# Mainboard.net
KiCad netlist of a schematic drawn in Altium Designer
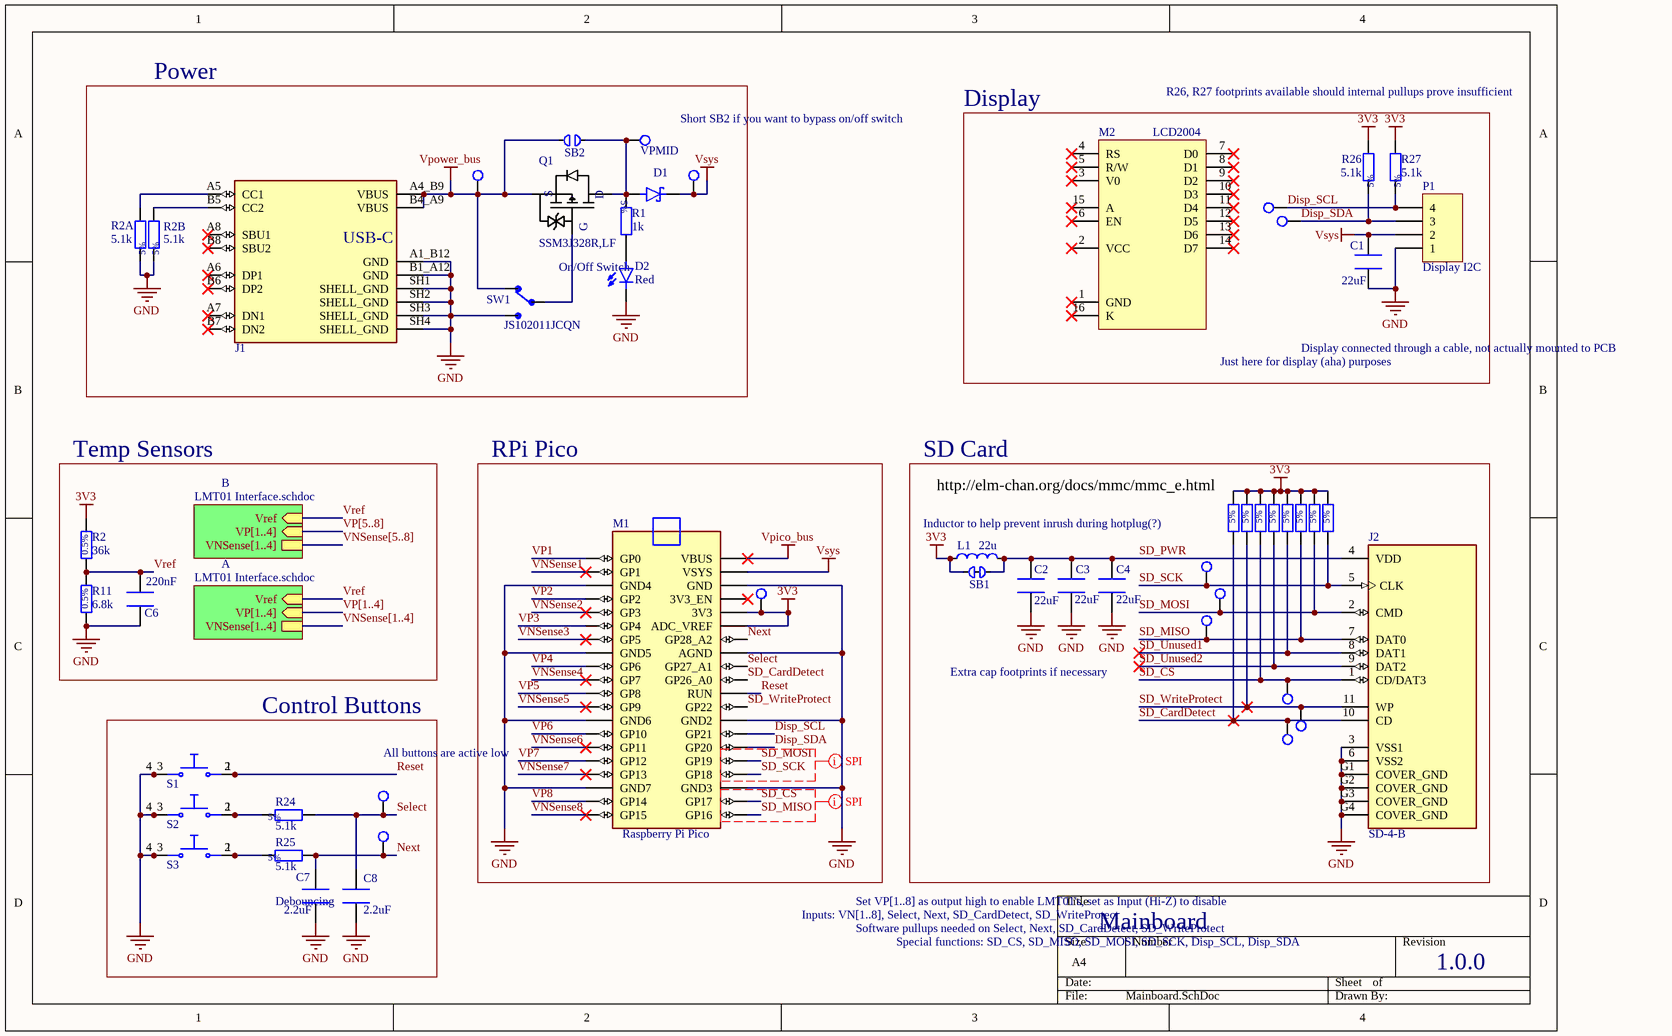
[diagram p0: Mainboard.SchDoc]

(export (version "E")
  (design (tool "Eeschema 10.0.6"))
  (components
    (comp (ref "3V3")
      (value "Test Pad")
      (footprint "Test Pad")
      (libsource (lib "General Components") (part "Test Pad"))
    )
    (comp (ref "C1")
      (value "22uF")
      (footprint "APSS Prototype Parts:CAPACITOR_0805_2012M-70N")
      (description "Passive - Capacitor, X5R, 22uF Max, 6.3V, 0805 (2012 Metric), ±20%, -55°C ~ 85°C. 8.8uF @ 5V")
      (fields (field (name "TOLERANCE") "±20%") (field (name "MF PART NO.") "C0805C226M9PACTU"))
      (libsource (lib "APSS Prototype Parts") (part "C0805C226M9PACTU"))
    )
    (comp (ref "C2")
      (value "22uF")
      (footprint "APSS Prototype Parts:CAPACITOR_0805_2012M-70N")
      (fields
        (field (name "TOLERANCE") "±20%")
        (field (name "MF PART NO.") "GRM21BR61C226ME44L")
        (field (name "APSS STANDARD PART") "APSS Standard")
      )
      (libsource (lib "APSS Prototype Parts") (part "GRM21BR61C226ME44L"))
    )
    (comp (ref "C3")
      (value "22uF")
      (footprint "APSS Prototype Parts:CAPACITOR_0805_2012M-70N")
      (fields
        (field (name "TOLERANCE") "±20%")
        (field (name "MF PART NO.") "GRM21BR61C226ME44L")
        (field (name "APSS STANDARD PART") "APSS Standard")
      )
      (libsource (lib "APSS Prototype Parts") (part "GRM21BR61C226ME44L"))
    )
    (comp (ref "C4")
      (value "22uF")
      (footprint "APSS Prototype Parts:CAPACITOR_0805_2012M-70N")
      (fields
        (field (name "TOLERANCE") "±20%")
        (field (name "MF PART NO.") "GRM21BR61C226ME44L")
        (field (name "APSS STANDARD PART") "APSS Standard")
      )
      (libsource (lib "APSS Prototype Parts") (part "GRM21BR61C226ME44L"))
    )
    (comp (ref "C6")
      (value "220nF")
      (footprint "APSS Prototype Parts:CAPACITOR_0805_2012M-70N")
      (fields
        (field (name "TOLERANCE") "±10%")
        (field (name "MF PART NO.") "C0805C224K1RAC7800")
        (field (name "APSS STANDARD PART") "APSS Standard")
      )
      (libsource (lib "APSS Prototype Parts") (part "C0805C224K1RAC7800"))
    )
    (comp (ref "C7")
      (value "2.2uF")
      (footprint "APSS Prototype Parts:CAPACITOR_0805_2012M-70N")
      (fields
        (field (name "TOLERANCE") "±10%")
        (field (name "MF PART NO.") "C0805C225K8PACTU")
        (field (name "APSS STANDARD PART") "APSS Standard")
      )
      (libsource (lib "APSS Prototype Parts") (part "C0805C225K8PACTU"))
    )
    (comp (ref "C8")
      (value "2.2uF")
      (footprint "APSS Prototype Parts:CAPACITOR_0805_2012M-70N")
      (fields
        (field (name "TOLERANCE") "±10%")
        (field (name "MF PART NO.") "C0805C225K8PACTU")
        (field (name "APSS STANDARD PART") "APSS Standard")
      )
      (libsource (lib "APSS Prototype Parts") (part "C0805C225K8PACTU"))
    )
    (comp (ref "CS")
      (value "Test Pad")
      (footprint "Test Pad")
      (libsource (lib "General Components") (part "Test Pad"))
    )
    (comp (ref "D1")
      (value "SS0520_R1_00001")
      (footprint "APSS Prototype Parts:SOD123-1.35mm-N")
      (description "Diode - Low Forward Voltage, Schottky, 385 mV @ 500 mA, 75 µA Reverse @ 10 V, SOD-123")
      (fields (field (name "APSS STANDARD PART") "APSS Standard"))
      (libsource (lib "APSS Prototype Parts") (part "SS0520_R1_00001"))
    )
    (comp (ref "D2")
      (value "LTST-C190 Series")
      (footprint "APSS Prototype Parts:LED_0603_1608M_0.80mm")
      (description "Diode - LED, 0603")
      (fields
        (field (name "APSS STANDARD PART") "APSS Standard")
        (field (name "MF PART NO.") "LTST-C190KAKT")
        (field (name "COLOUR") "Red")
      )
      (libsource (lib "APSS Prototype Parts") (part "LTST-C190 Series"))
    )
    (comp (ref "J1")
      (value "USB4105-GF-A")
      (footprint "GCT_USB4105-GF-A")
      (fields (field (name "APSS STANDARD PART") "APSS Standard"))
      (libsource (lib "APSS Prototype Parts") (part "USB4105-GF-A"))
    )
    (comp (ref "J2") (value "SD-4-B") (footprint "CUI_SD-4-B") (libsource (lib "SD-4-B") (part "SD-4-B")))
    (comp (ref "L1")
      (value "22u")
      (footprint "CAPACITOR_1210_3225M_270N")
      (description "Passive - Inductor, Generic")
      (fields (field (name "TOLERANCE") "±20%") (field (name "MF PART NO.") "LSQPA322525T220MR"))
      (libsource (lib "General Components") (part "Generic Inductor"))
    )
    (comp (ref "M1")
      (value "RASPBERRY_PI_PICO")
      (footprint "RASPBERRY_PI_PICO:RASPBERRY_PI_PICO_SOCKETED")
      (fields (field (name "MF PART NO.") "SC0917"))
      (libsource (lib "RASPBERRY_PI_PICO") (part "RASPBERRY_PI_PICO"))
    )
    (comp (ref "M2")
      (value "LCD2004")
      (footprint "LCD2004:LCD2004")
      (fields (field (name "MF PART NO.") "CN0296D"))
      (libsource (lib "LCD2004") (part "LCD2004"))
    )
    (comp (ref "MISO")
      (value "Test Pad")
      (footprint "Test Pad")
      (libsource (lib "General Components") (part "Test Pad"))
    )
    (comp (ref "MOSI")
      (value "Test Pad")
      (footprint "Test Pad")
      (libsource (lib "General Components") (part "Test Pad"))
    )
    (comp (ref "NXT")
      (value "Test Pad")
      (footprint "Test Pad")
      (libsource (lib "General Components") (part "Test Pad"))
    )
    (comp (ref "P1")
      (value "Display I2C")
      (footprint "HDR1X4H")
      (description "Header, 4-Pin, Right Angle")
      (libsource (lib "Miscellaneous Connectors") (part "Header 4H"))
    )
    (comp (ref "Q1")
      (value "SSM3J328R,LF")
      (footprint "APSS Prototype Parts:SOT23F-3-0.8mm")
      (description "Transistor - MOSFET, P-Channel SSM3J328R,LF")
      (fields (field (name "POWER") "1W") (field (name "APSS STANDARD PART") "APSS Standard"))
      (libsource (lib "APSS Prototype Parts") (part "SSM3J328R,LF"))
    )
    (comp (ref "R1")
      (value "1k")
      (footprint "APSS Prototype Parts:Resistor_0805_2012M-50N")
      (fields
        (field (name "TOLERANCE") "5%")
        (field (name "POWER") "1/8W")
        (field (name "APSS STANDARD PART") "APSS Standard")
      )
      (libsource (lib "") (part "RMCF0805JT Series_1"))
    )
    (comp (ref "R2")
      (value "36k")
      (footprint "APSS Prototype Parts:Resistor_0805_2012M-50N")
      (fields
        (field (name "TOLERANCE") "0.5%")
        (field (name "POWER") "1/8W")
        (field (name "APSS STANDARD PART") "APSS Standard")
      )
      (libsource (lib "APSS Prototype Parts") (part "RG2012P-xxx-D-T5 Series"))
    )
    (comp (ref "R2A")
      (value "5.1k")
      (footprint "APSS Prototype Parts:Resistor_0805_2012M-50N")
      (fields
        (field (name "TOLERANCE") "5%")
        (field (name "POWER") "1/8W")
        (field (name "MF PART NO.") "RMCF0805JT5K10")
      )
      (libsource (lib "") (part "RMCF0805JT Series_3"))
    )
    (comp (ref "R2B")
      (value "5.1k")
      (footprint "APSS Prototype Parts:Resistor_0805_2012M-50N")
      (fields
        (field (name "TOLERANCE") "5%")
        (field (name "POWER") "1/8W")
        (field (name "MF PART NO.") "RMCF0805JT5K10")
      )
      (libsource (lib "") (part "RMCF0805JT Series_3"))
    )
    (comp (ref "R3")
      (value "47k")
      (footprint "APSS Prototype Parts:Resistor_0805_2012M-50N")
      (fields
        (field (name "TOLERANCE") "5%")
        (field (name "POWER") "1/8W")
        (field (name "APSS STANDARD PART") "APSS Standard")
      )
      (libsource (lib "APSS Prototype Parts") (part "RMCF0805JT Series"))
    )
    (comp (ref "R4")
      (value "47k")
      (footprint "APSS Prototype Parts:Resistor_0805_2012M-50N")
      (fields
        (field (name "TOLERANCE") "5%")
        (field (name "POWER") "1/8W")
        (field (name "APSS STANDARD PART") "APSS Standard")
      )
      (libsource (lib "APSS Prototype Parts") (part "RMCF0805JT Series"))
    )
    (comp (ref "R5")
      (value "47k")
      (footprint "APSS Prototype Parts:Resistor_0805_2012M-50N")
      (fields
        (field (name "TOLERANCE") "5%")
        (field (name "POWER") "1/8W")
        (field (name "APSS STANDARD PART") "APSS Standard")
      )
      (libsource (lib "APSS Prototype Parts") (part "RMCF0805JT Series"))
    )
    (comp (ref "R6")
      (value "47k")
      (footprint "APSS Prototype Parts:Resistor_0805_2012M-50N")
      (fields
        (field (name "TOLERANCE") "5%")
        (field (name "POWER") "1/8W")
        (field (name "APSS STANDARD PART") "APSS Standard")
      )
      (libsource (lib "APSS Prototype Parts") (part "RMCF0805JT Series"))
    )
    (comp (ref "R7")
      (value "47k")
      (footprint "APSS Prototype Parts:Resistor_0805_2012M-50N")
      (fields
        (field (name "TOLERANCE") "5%")
        (field (name "POWER") "1/8W")
        (field (name "APSS STANDARD PART") "APSS Standard")
      )
      (libsource (lib "APSS Prototype Parts") (part "RMCF0805JT Series"))
    )
    (comp (ref "R8")
      (value "47k")
      (footprint "APSS Prototype Parts:Resistor_0805_2012M-50N")
      (fields
        (field (name "TOLERANCE") "5%")
        (field (name "POWER") "1/8W")
        (field (name "APSS STANDARD PART") "APSS Standard")
      )
      (libsource (lib "APSS Prototype Parts") (part "RMCF0805JT Series"))
    )
    (comp (ref "R9")
      (value "47k")
      (footprint "APSS Prototype Parts:Resistor_0805_2012M-50N")
      (fields
        (field (name "TOLERANCE") "5%")
        (field (name "POWER") "1/8W")
        (field (name "APSS STANDARD PART") "APSS Standard")
      )
      (libsource (lib "APSS Prototype Parts") (part "RMCF0805JT Series"))
    )
    (comp (ref "R10")
      (value "47k")
      (footprint "APSS Prototype Parts:Resistor_0805_2012M-50N")
      (fields
        (field (name "TOLERANCE") "5%")
        (field (name "POWER") "1/8W")
        (field (name "APSS STANDARD PART") "APSS Standard")
      )
      (libsource (lib "APSS Prototype Parts") (part "RMCF0805JT Series"))
    )
    (comp (ref "R11")
      (value "6.8k")
      (footprint "APSS Prototype Parts:Resistor_0805_2012M-50N")
      (fields
        (field (name "TOLERANCE") "0.5%")
        (field (name "POWER") "1/8W")
        (field (name "APSS STANDARD PART") "APSS Standard")
      )
      (libsource (lib "APSS Prototype Parts") (part "RG2012P-xxx-D-T5 Series"))
    )
    (comp (ref "R24")
      (value "5.1k")
      (footprint "APSS Prototype Parts:Resistor_0805_2012M-50N")
      (fields
        (field (name "TOLERANCE") "5%")
        (field (name "POWER") "1/8W")
        (field (name "MF PART NO.") "RMCF0805JT5K10")
      )
      (libsource (lib "") (part "RMCF0805JT Series_2"))
    )
    (comp (ref "R25")
      (value "5.1k")
      (footprint "APSS Prototype Parts:Resistor_0805_2012M-50N")
      (fields
        (field (name "TOLERANCE") "5%")
        (field (name "POWER") "1/8W")
        (field (name "MF PART NO.") "RMCF0805JT5K10")
      )
      (libsource (lib "") (part "RMCF0805JT Series_2"))
    )
    (comp (ref "R26")
      (value "5.1k")
      (footprint "APSS Prototype Parts:Resistor_0805_2012M-50N")
      (fields
        (field (name "TOLERANCE") "5%")
        (field (name "POWER") "1/8W")
        (field (name "MF PART NO.") "RMCF0805JT5K10")
      )
      (libsource (lib "") (part "RMCF0805JT Series_3"))
    )
    (comp (ref "R27")
      (value "5.1k")
      (footprint "APSS Prototype Parts:Resistor_0805_2012M-50N")
      (fields
        (field (name "TOLERANCE") "5%")
        (field (name "POWER") "1/8W")
        (field (name "MF PART NO.") "RMCF0805JT5K10")
      )
      (libsource (lib "") (part "RMCF0805JT Series_3"))
    )
    (comp (ref "S1")
      (value "PTS645SL43SMTR92LFS")
      (footprint "SW_PTS645SL43SMTR92LFS")
      (description "Switch - SPST, Momentary, Normally Open, 50mA @ 12VDC")
      (fields
        (field (name "APSS STANDARD PART") "APSS Standard")
        (field (name "MF PART NO.") "SW_PTS645SL43SMTR92LFS")
      )
      (libsource (lib "APSS Prototype Parts") (part "PTS645SL43SMTR92LFS"))
    )
    (comp (ref "S2")
      (value "PTS645SL43SMTR92LFS")
      (footprint "SW_PTS645SL43SMTR92LFS")
      (description "Switch - SPST, Momentary, Normally Open, 50mA @ 12VDC")
      (fields
        (field (name "APSS STANDARD PART") "APSS Standard")
        (field (name "MF PART NO.") "SW_PTS645SL43SMTR92LFS")
      )
      (libsource (lib "APSS Prototype Parts") (part "PTS645SL43SMTR92LFS"))
    )
    (comp (ref "S3")
      (value "PTS645SL43SMTR92LFS")
      (footprint "SW_PTS645SL43SMTR92LFS")
      (description "Switch - SPST, Momentary, Normally Open, 50mA @ 12VDC")
      (fields
        (field (name "APSS STANDARD PART") "APSS Standard")
        (field (name "MF PART NO.") "SW_PTS645SL43SMTR92LFS")
      )
      (libsource (lib "APSS Prototype Parts") (part "PTS645SL43SMTR92LFS"))
    )
    (comp (ref "SB1")
      (value "Solder Jumper Normally Closed 0201")
      (footprint "General Components:Solder Bridge Closed 0201")
      (libsource (lib "General Components") (part "Solder Jumper Normally Closed 0201"))
    )
    (comp (ref "SB2")
      (value "Solder Jumper Normally Open 0201")
      (footprint "General Components:Solder Bridge Open 0201")
      (libsource (lib "General Components") (part "Solder Jumper Normally Open 0201"))
    )
    (comp (ref "SCK")
      (value "Test Pad")
      (footprint "Test Pad")
      (libsource (lib "General Components") (part "Test Pad"))
    )
    (comp (ref "SCL")
      (value "Test Pad")
      (footprint "Test Pad")
      (libsource (lib "General Components") (part "Test Pad"))
    )
    (comp (ref "SDA")
      (value "Test Pad")
      (footprint "Test Pad")
      (libsource (lib "General Components") (part "Test Pad"))
    )
    (comp (ref "SD_CD")
      (value "Test Pad")
      (footprint "Test Pad")
      (libsource (lib "General Components") (part "Test Pad"))
    )
    (comp (ref "SD_WP")
      (value "Test Pad")
      (footprint "Test Pad")
      (libsource (lib "General Components") (part "Test Pad"))
    )
    (comp (ref "SEL")
      (value "Test Pad")
      (footprint "Test Pad")
      (libsource (lib "General Components") (part "Test Pad"))
    )
    (comp (ref "SW1")
      (value "JS102011JCQN")
      (footprint "SW_JS102011JCQN:SW_JS102011JCQN")
      (description "Switch Slide Spdt 300ma 6v")
      (libsource (lib "JS102011JCQN") (part "JS102011JCQN"))
    )
    (comp (ref "VPBUS")
      (value "Test Pad")
      (footprint "Test Pad")
      (libsource (lib "General Components") (part "Test Pad"))
    )
    (comp (ref "VPMID")
      (value "Test Pad")
      (footprint "Test Pad")
      (libsource (lib "General Components") (part "Test Pad"))
    )
    (comp (ref "VSYS")
      (value "Test Pad")
      (footprint "Test Pad")
      (libsource (lib "General Components") (part "Test Pad"))
    )
  )
  (nets
    (net (code "1") (name "/Disp_SCL") (class "Default")
      (node (ref "M1") (pin "GP21") (pinfunction "GP21_GP21") (pintype "bidirectional"))
      (node (ref "P1") (pin "4") (pinfunction "4_4") (pintype "passive"))
      (node (ref "R27") (pin "1") (pinfunction "1_1") (pintype "passive"))
      (node (ref "SCL") (pin "1") (pinfunction "0_1") (pintype "passive"))
    )
    (net (code "2") (name "/Disp_SDA") (class "Default")
      (node (ref "M1") (pin "GP20") (pinfunction "GP20_GP20") (pintype "bidirectional"))
      (node (ref "P1") (pin "3") (pinfunction "3_3") (pintype "passive"))
      (node (ref "R26") (pin "1") (pinfunction "1_1") (pintype "passive"))
      (node (ref "SDA") (pin "1") (pinfunction "0_1") (pintype "passive"))
    )
    (net (code "3") (name "/Next") (class "Default")
      (node (ref "C7") (pin "2") (pinfunction "2_2") (pintype "passive"))
      (node (ref "M1") (pin "GP28_A2") (pinfunction "GP28_A2_GP28_A2") (pintype "bidirectional"))
      (node (ref "NXT") (pin "1") (pinfunction "0_1") (pintype "passive"))
      (node (ref "R25") (pin "2") (pinfunction "2_2") (pintype "passive"))
    )
    (net (code "4") (name "/Reset") (class "Default")
      (node (ref "M1") (pin "RUN") (pinfunction "RUN_RUN") (pintype "passive"))
      (node (ref "S1") (pin "1") (pinfunction "1_1") (pintype "passive"))
      (node (ref "S1") (pin "2") (pinfunction ",_2_2") (pintype "passive"))
    )
    (net (code "5") (name "/SD_CS") (class "Default")
      (node (ref "CS") (pin "1") (pinfunction "0_1") (pintype "passive"))
      (node (ref "J2") (pin "1") (pinfunction "CD/DAT3_1") (pintype "bidirectional"))
      (node (ref "M1") (pin "GP17") (pinfunction "GP17_GP17") (pintype "bidirectional"))
      (node (ref "R5") (pin "1") (pinfunction "1_1") (pintype "passive"))
    )
    (net (code "6") (name "/SD_CardDetect") (class "Default")
      (node (ref "J2") (pin "10") (pinfunction "CD_10") (pintype "passive"))
      (node (ref "M1") (pin "GP26_A0") (pinfunction "GP26_A0_GP26_A0") (pintype "bidirectional"))
      (node (ref "R3") (pin "1") (pinfunction "1_1") (pintype "passive"))
      (node (ref "SD_CD") (pin "1") (pinfunction "0_1") (pintype "passive"))
    )
    (net (code "7") (name "/SD_MISO") (class "Default")
      (node (ref "J2") (pin "7") (pinfunction "DAT0_7") (pintype "bidirectional"))
      (node (ref "M1") (pin "GP16") (pinfunction "GP16_GP16") (pintype "bidirectional"))
      (node (ref "MISO") (pin "1") (pinfunction "0_1") (pintype "passive"))
      (node (ref "R8") (pin "1") (pinfunction "1_1") (pintype "passive"))
    )
    (net (code "8") (name "/SD_MOSI") (class "Default")
      (node (ref "J2") (pin "2") (pinfunction "CMD_2") (pintype "bidirectional"))
      (node (ref "M1") (pin "GP19") (pinfunction "GP19_GP19") (pintype "bidirectional"))
      (node (ref "MOSI") (pin "1") (pinfunction "0_1") (pintype "passive"))
      (node (ref "R9") (pin "1") (pinfunction "1_1") (pintype "passive"))
    )
    (net (code "9") (name "/SD_PWR") (class "Default")
      (node (ref "C2") (pin "2") (pinfunction "2_2") (pintype "passive"))
      (node (ref "C3") (pin "2") (pinfunction "2_2") (pintype "passive"))
      (node (ref "C4") (pin "2") (pinfunction "2_2") (pintype "passive"))
      (node (ref "J2") (pin "4") (pinfunction "VDD_4") (pintype "power_in"))
      (node (ref "L1") (pin "2") (pinfunction "2_2") (pintype "passive"))
      (node (ref "SB1") (pin "2") (pinfunction "2_2") (pintype "passive"))
    )
    (net (code "10") (name "/SD_SCK") (class "Default")
      (node (ref "J2") (pin "5") (pinfunction "CLK_5") (pintype "input"))
      (node (ref "M1") (pin "GP18") (pinfunction "GP18_GP18") (pintype "bidirectional"))
      (node (ref "R10") (pin "1") (pinfunction "1_1") (pintype "passive"))
      (node (ref "SCK") (pin "1") (pinfunction "0_1") (pintype "passive"))
    )
    (net (code "11") (name "/SD_Unused1") (class "Default")
      (node (ref "J2") (pin "8") (pinfunction "DAT1_8") (pintype "bidirectional"))
      (node (ref "R7") (pin "1") (pinfunction "1_1") (pintype "passive"))
    )
    (net (code "12") (name "/SD_Unused2") (class "Default")
      (node (ref "J2") (pin "9") (pinfunction "DAT2_9") (pintype "bidirectional"))
      (node (ref "R6") (pin "1") (pinfunction "1_1") (pintype "passive"))
    )
    (net (code "13") (name "/SD_WriteProtect") (class "Default")
      (node (ref "J2") (pin "11") (pinfunction "WP_11") (pintype "passive"))
      (node (ref "M1") (pin "GP22") (pinfunction "GP22_GP22") (pintype "bidirectional"))
      (node (ref "R4") (pin "1") (pinfunction "1_1") (pintype "passive"))
      (node (ref "SD_WP") (pin "1") (pinfunction "0_1") (pintype "passive"))
    )
    (net (code "14") (name "/Select") (class "Default")
      (node (ref "C8") (pin "2") (pinfunction "2_2") (pintype "passive"))
      (node (ref "M1") (pin "GP27_A1") (pinfunction "GP27_A1_GP27_A1") (pintype "bidirectional"))
      (node (ref "R24") (pin "2") (pinfunction "2_2") (pintype "passive"))
      (node (ref "SEL") (pin "1") (pinfunction "0_1") (pintype "passive"))
    )
    (net (code "15") (name "/VNSense1") (class "Default")
      (node (ref "M1") (pin "GP1") (pinfunction "GP1_GP1") (pintype "bidirectional+no_connect"))
    )
    (net (code "16") (name "/VNSense2") (class "Default")
      (node (ref "M1") (pin "GP3") (pinfunction "GP3_GP3") (pintype "bidirectional+no_connect"))
    )
    (net (code "17") (name "/VNSense3") (class "Default")
      (node (ref "M1") (pin "GP5") (pinfunction "GP5_GP5") (pintype "bidirectional+no_connect"))
    )
    (net (code "18") (name "/VNSense4") (class "Default")
      (node (ref "M1") (pin "GP7") (pinfunction "GP7_GP7") (pintype "bidirectional+no_connect"))
    )
    (net (code "19") (name "/VNSense5") (class "Default")
      (node (ref "M1") (pin "GP9") (pinfunction "GP9_GP9") (pintype "bidirectional+no_connect"))
    )
    (net (code "20") (name "/VNSense6") (class "Default")
      (node (ref "M1") (pin "GP11") (pinfunction "GP11_GP11") (pintype "bidirectional+no_connect"))
    )
    (net (code "21") (name "/VNSense7") (class "Default")
      (node (ref "M1") (pin "GP13") (pinfunction "GP13_GP13") (pintype "bidirectional+no_connect"))
    )
    (net (code "22") (name "/VNSense8") (class "Default")
      (node (ref "M1") (pin "GP15") (pinfunction "GP15_GP15") (pintype "bidirectional+no_connect"))
    )
    (net (code "25") (name "/VP1") (class "Default")
      (node (ref "M1") (pin "GP0") (pinfunction "GP0_GP0") (pintype "bidirectional"))
    )
    (net (code "26") (name "/VP2") (class "Default")
      (node (ref "M1") (pin "GP2") (pinfunction "GP2_GP2") (pintype "bidirectional"))
    )
    (net (code "27") (name "/VP3") (class "Default")
      (node (ref "M1") (pin "GP4") (pinfunction "GP4_GP4") (pintype "bidirectional"))
    )
    (net (code "28") (name "/VP4") (class "Default")
      (node (ref "M1") (pin "GP6") (pinfunction "GP6_GP6") (pintype "bidirectional"))
    )
    (net (code "29") (name "/VP5") (class "Default")
      (node (ref "M1") (pin "GP8") (pinfunction "GP8_GP8") (pintype "bidirectional"))
    )
    (net (code "30") (name "/VP6") (class "Default")
      (node (ref "M1") (pin "GP10") (pinfunction "GP10_GP10") (pintype "bidirectional"))
    )
    (net (code "31") (name "/VP7") (class "Default")
      (node (ref "M1") (pin "GP12") (pinfunction "GP12_GP12") (pintype "bidirectional"))
    )
    (net (code "32") (name "/VP8") (class "Default")
      (node (ref "M1") (pin "GP14") (pinfunction "GP14_GP14") (pintype "bidirectional"))
    )
    (net (code "35") (name "/Vref") (class "Default")
      (node (ref "C6") (pin "2") (pinfunction "2_2") (pintype "passive"))
      (node (ref "R11") (pin "2") (pinfunction "2_2") (pintype "passive"))
      (node (ref "R2") (pin "1") (pinfunction "1_1") (pintype "passive"))
    )
    (net (code "36") (name "3V3") (class "Default")
      (node (ref "3V3") (pin "1") (pinfunction "0_1") (pintype "passive"))
      (node (ref "L1") (pin "1") (pinfunction "1_1") (pintype "passive"))
      (node (ref "M1") (pin "3V3") (pinfunction "3V3_3V3") (pintype "passive"))
      (node (ref "M1") (pin "ADC_VREF") (pinfunction "ADC_VREF_ADC_VREF") (pintype "passive"))
      (node (ref "R10") (pin "2") (pinfunction "2_2") (pintype "passive"))
      (node (ref "R2") (pin "2") (pinfunction "2_2") (pintype "passive"))
      (node (ref "R26") (pin "2") (pinfunction "2_2") (pintype "passive"))
      (node (ref "R27") (pin "2") (pinfunction "2_2") (pintype "passive"))
      (node (ref "R3") (pin "2") (pinfunction "2_2") (pintype "passive"))
      (node (ref "R4") (pin "2") (pinfunction "2_2") (pintype "passive"))
      (node (ref "R5") (pin "2") (pinfunction "2_2") (pintype "passive"))
      (node (ref "R6") (pin "2") (pinfunction "2_2") (pintype "passive"))
      (node (ref "R7") (pin "2") (pinfunction "2_2") (pintype "passive"))
      (node (ref "R8") (pin "2") (pinfunction "2_2") (pintype "passive"))
      (node (ref "R9") (pin "2") (pinfunction "2_2") (pintype "passive"))
      (node (ref "SB1") (pin "1") (pinfunction "1_1") (pintype "passive"))
    )
    (net (code "37") (name "GND") (class "Default")
      (node (ref "C1") (pin "1") (pinfunction "1_1") (pintype "passive"))
      (node (ref "C2") (pin "1") (pinfunction "1_1") (pintype "passive"))
      (node (ref "C3") (pin "1") (pinfunction "1_1") (pintype "passive"))
      (node (ref "C4") (pin "1") (pinfunction "1_1") (pintype "passive"))
      (node (ref "C6") (pin "1") (pinfunction "1_1") (pintype "passive"))
      (node (ref "C7") (pin "1") (pinfunction "1_1") (pintype "passive"))
      (node (ref "C8") (pin "1") (pinfunction "1_1") (pintype "passive"))
      (node (ref "D2") (pin "C") (pinfunction "C_C") (pintype "passive"))
      (node (ref "J1") (pin "A1_B12") (pinfunction "GND_A1_B12") (pintype "power_in"))
      (node (ref "J1") (pin "B1_A12") (pinfunction "GND_B1_A12") (pintype "power_in"))
      (node (ref "J1") (pin "SH1") (pinfunction "SHELL_GND_SH1") (pintype "power_in"))
      (node (ref "J1") (pin "SH2") (pinfunction "SHELL_GND_SH2") (pintype "power_in"))
      (node (ref "J1") (pin "SH3") (pinfunction "SHELL_GND_SH3") (pintype "power_in"))
      (node (ref "J1") (pin "SH4") (pinfunction "SHELL_GND_SH4") (pintype "power_in"))
      (node (ref "J2") (pin "3") (pinfunction "VSS1_3") (pintype "power_in"))
      (node (ref "J2") (pin "6") (pinfunction "VSS2_6") (pintype "power_in"))
      (node (ref "J2") (pin "G1") (pinfunction "COVER_GND_G1") (pintype "power_in"))
      (node (ref "J2") (pin "G2") (pinfunction "COVER_GND_G2") (pintype "power_in"))
      (node (ref "J2") (pin "G3") (pinfunction "COVER_GND_G3") (pintype "power_in"))
      (node (ref "J2") (pin "G4") (pinfunction "COVER_GND_G4") (pintype "power_in"))
      (node (ref "M1") (pin "AGND") (pinfunction "AGND_AGND") (pintype "passive"))
      (node (ref "M1") (pin "GND") (pinfunction "GND_GND") (pintype "passive"))
      (node (ref "M1") (pin "GND2") (pinfunction "GND2_GND2") (pintype "passive"))
      (node (ref "M1") (pin "GND3") (pinfunction "GND3_GND3") (pintype "passive"))
      (node (ref "M1") (pin "GND4") (pinfunction "GND4_GND4") (pintype "passive"))
      (node (ref "M1") (pin "GND5") (pinfunction "GND5_GND5") (pintype "passive"))
      (node (ref "M1") (pin "GND6") (pinfunction "GND6_GND6") (pintype "passive"))
      (node (ref "M1") (pin "GND7") (pinfunction "GND7_GND7") (pintype "passive"))
      (node (ref "P1") (pin "1") (pinfunction "1_1") (pintype "passive"))
      (node (ref "R11") (pin "1") (pinfunction "1_1") (pintype "passive"))
      (node (ref "R2A") (pin "1") (pinfunction "1_1") (pintype "passive"))
      (node (ref "R2B") (pin "1") (pinfunction "1_1") (pintype "passive"))
      (node (ref "S1") (pin "3") (pinfunction "3_3") (pintype "passive"))
      (node (ref "S1") (pin "4") (pinfunction "4_4") (pintype "passive"))
      (node (ref "S2") (pin "3") (pinfunction "3_3") (pintype "passive"))
      (node (ref "S2") (pin "4") (pinfunction "4_4") (pintype "passive"))
      (node (ref "S3") (pin "3") (pinfunction "3_3") (pintype "passive"))
      (node (ref "S3") (pin "4") (pinfunction "4_4") (pintype "passive"))
      (node (ref "SW1") (pin "3") (pinfunction "3_3") (pintype "passive"))
    )
    (net (code "38") (name "Net-(D2-PadA)") (class "Default")
      (node (ref "D2") (pin "A") (pinfunction "A_A") (pintype "passive"))
      (node (ref "R1") (pin "2") (pinfunction "2_2") (pintype "passive"))
    )
    (net (code "39") (name "Net-(J1-CC1)") (class "Default")
      (node (ref "J1") (pin "A5") (pinfunction "CC1_A5") (pintype "bidirectional"))
      (node (ref "R2A") (pin "2") (pinfunction "2_2") (pintype "passive"))
    )
    (net (code "40") (name "Net-(J1-CC2)") (class "Default")
      (node (ref "J1") (pin "B5") (pinfunction "CC2_B5") (pintype "bidirectional"))
      (node (ref "R2B") (pin "2") (pinfunction "2_2") (pintype "passive"))
    )
    (net (code "41") (name "Net-(Q1-D)") (class "Default")
      (node (ref "D1") (pin "A") (pinfunction "A_A") (pintype "passive"))
      (node (ref "Q1") (pin "3") (pinfunction "D_3") (pintype "passive"))
      (node (ref "R1") (pin "1") (pinfunction "1_1") (pintype "passive"))
      (node (ref "SB2") (pin "1") (pinfunction "1_1") (pintype "passive"))
      (node (ref "VPMID") (pin "1") (pinfunction "0_1") (pintype "passive"))
    )
    (net (code "42") (name "Net-(Q1-G)") (class "Default")
      (node (ref "Q1") (pin "1") (pinfunction "G_1") (pintype "passive"))
      (node (ref "SW1") (pin "2") (pinfunction "2_2") (pintype "passive"))
    )
    (net (code "43") (name "Net-(S2-,_2)") (class "Default")
      (node (ref "R24") (pin "1") (pinfunction "1_1") (pintype "passive"))
      (node (ref "S2") (pin "1") (pinfunction "1_1") (pintype "passive"))
      (node (ref "S2") (pin "2") (pinfunction ",_2_2") (pintype "passive"))
    )
    (net (code "44") (name "Net-(S3-,_2)") (class "Default")
      (node (ref "R25") (pin "1") (pinfunction "1_1") (pintype "passive"))
      (node (ref "S3") (pin "1") (pinfunction "1_1") (pintype "passive"))
      (node (ref "S3") (pin "2") (pinfunction ",_2_2") (pintype "passive"))
    )
    (net (code "45") (name "Vpico_bus") (class "Default")
      (node (ref "M1") (pin "VBUS") (pinfunction "VBUS_VBUS") (pintype "passive"))
    )
    (net (code "46") (name "Vpower_bus") (class "Default")
      (node (ref "J1") (pin "A4_B9") (pinfunction "VBUS_A4_B9") (pintype "power_in"))
      (node (ref "J1") (pin "B4_A9") (pinfunction "VBUS_B4_A9") (pintype "power_in"))
      (node (ref "Q1") (pin "2") (pinfunction "S_2") (pintype "passive"))
      (node (ref "SB2") (pin "2") (pinfunction "2_2") (pintype "passive"))
      (node (ref "SW1") (pin "1") (pinfunction "1_1") (pintype "passive"))
      (node (ref "VPBUS") (pin "1") (pinfunction "0_1") (pintype "passive"))
    )
    (net (code "47") (name "Vsys") (class "Default")
      (node (ref "C1") (pin "2") (pinfunction "2_2") (pintype "passive"))
      (node (ref "D1") (pin "C") (pinfunction "C_C") (pintype "passive"))
      (node (ref "M1") (pin "VSYS") (pinfunction "VSYS_VSYS") (pintype "passive"))
      (node (ref "P1") (pin "2") (pinfunction "2_2") (pintype "passive"))
      (node (ref "VSYS") (pin "1") (pinfunction "0_1") (pintype "passive"))
    )
    (net (code "48") (name "unconnected-(J1-DN1-PadA7)") (class "Default")
      (node (ref "J1") (pin "A7") (pinfunction "DN1_A7") (pintype "bidirectional+no_connect"))
    )
    (net (code "49") (name "unconnected-(J1-DN2-PadB7)") (class "Default")
      (node (ref "J1") (pin "B7") (pinfunction "DN2_B7") (pintype "bidirectional+no_connect"))
    )
    (net (code "50") (name "unconnected-(J1-DP1-PadA6)") (class "Default")
      (node (ref "J1") (pin "A6") (pinfunction "DP1_A6") (pintype "bidirectional+no_connect"))
    )
    (net (code "51") (name "unconnected-(J1-DP2-PadB6)") (class "Default")
      (node (ref "J1") (pin "B6") (pinfunction "DP2_B6") (pintype "bidirectional+no_connect"))
    )
    (net (code "52") (name "unconnected-(J1-SBU1-PadA8)") (class "Default")
      (node (ref "J1") (pin "A8") (pinfunction "SBU1_A8") (pintype "bidirectional+no_connect"))
    )
    (net (code "53") (name "unconnected-(J1-SBU2-PadB8)") (class "Default")
      (node (ref "J1") (pin "B8") (pinfunction "SBU2_B8") (pintype "bidirectional+no_connect"))
    )
    (net (code "54") (name "unconnected-(M1-Pad3V3_EN)") (class "Default")
      (node (ref "M1") (pin "3V3_EN") (pinfunction "3V3_EN_3V3_EN") (pintype "passive+no_connect"))
    )
    (net (code "55") (name "unconnected-(M2-A-Pad15)") (class "Default")
      (node (ref "M2") (pin "15") (pinfunction "A_15") (pintype "passive+no_connect"))
    )
    (net (code "56") (name "unconnected-(M2-D0-Pad7)") (class "Default")
      (node (ref "M2") (pin "7") (pinfunction "D0_7") (pintype "passive+no_connect"))
    )
    (net (code "57") (name "unconnected-(M2-D1-Pad8)") (class "Default")
      (node (ref "M2") (pin "8") (pinfunction "D1_8") (pintype "passive+no_connect"))
    )
    (net (code "58") (name "unconnected-(M2-D2-Pad9)") (class "Default")
      (node (ref "M2") (pin "9") (pinfunction "D2_9") (pintype "passive+no_connect"))
    )
    (net (code "59") (name "unconnected-(M2-D3-Pad10)") (class "Default")
      (node (ref "M2") (pin "10") (pinfunction "D3_10") (pintype "passive+no_connect"))
    )
    (net (code "60") (name "unconnected-(M2-D4-Pad11)") (class "Default")
      (node (ref "M2") (pin "11") (pinfunction "D4_11") (pintype "passive+no_connect"))
    )
    (net (code "61") (name "unconnected-(M2-D5-Pad12)") (class "Default")
      (node (ref "M2") (pin "12") (pinfunction "D5_12") (pintype "passive+no_connect"))
    )
    (net (code "62") (name "unconnected-(M2-D6-Pad13)") (class "Default")
      (node (ref "M2") (pin "13") (pinfunction "D6_13") (pintype "passive+no_connect"))
    )
    (net (code "63") (name "unconnected-(M2-D7-Pad14)") (class "Default")
      (node (ref "M2") (pin "14") (pinfunction "D7_14") (pintype "passive+no_connect"))
    )
    (net (code "64") (name "unconnected-(M2-EN-Pad6)") (class "Default")
      (node (ref "M2") (pin "6") (pinfunction "EN_6") (pintype "passive+no_connect"))
    )
    (net (code "65") (name "unconnected-(M2-GND-Pad1)") (class "Default")
      (node (ref "M2") (pin "1") (pinfunction "GND_1") (pintype "passive+no_connect"))
    )
    (net (code "66") (name "unconnected-(M2-K-Pad16)") (class "Default")
      (node (ref "M2") (pin "16") (pinfunction "K_16") (pintype "passive+no_connect"))
    )
    (net (code "67") (name "unconnected-(M2-RS-Pad4)") (class "Default")
      (node (ref "M2") (pin "4") (pinfunction "RS_4") (pintype "passive+no_connect"))
    )
    (net (code "68") (name "unconnected-(M2-R{slash}W-Pad5)") (class "Default")
      (node (ref "M2") (pin "5") (pinfunction "R/W_5") (pintype "passive+no_connect"))
    )
    (net (code "69") (name "unconnected-(M2-V0-Pad3)") (class "Default")
      (node (ref "M2") (pin "3") (pinfunction "V0_3") (pintype "passive+no_connect"))
    )
    (net (code "70") (name "unconnected-(M2-VCC-Pad2)") (class "Default")
      (node (ref "M2") (pin "2") (pinfunction "VCC_2") (pintype "passive+no_connect"))
    )
  )
)
